# PMODBob.net
KiCad netlist of a schematic drawn in Altium Designer
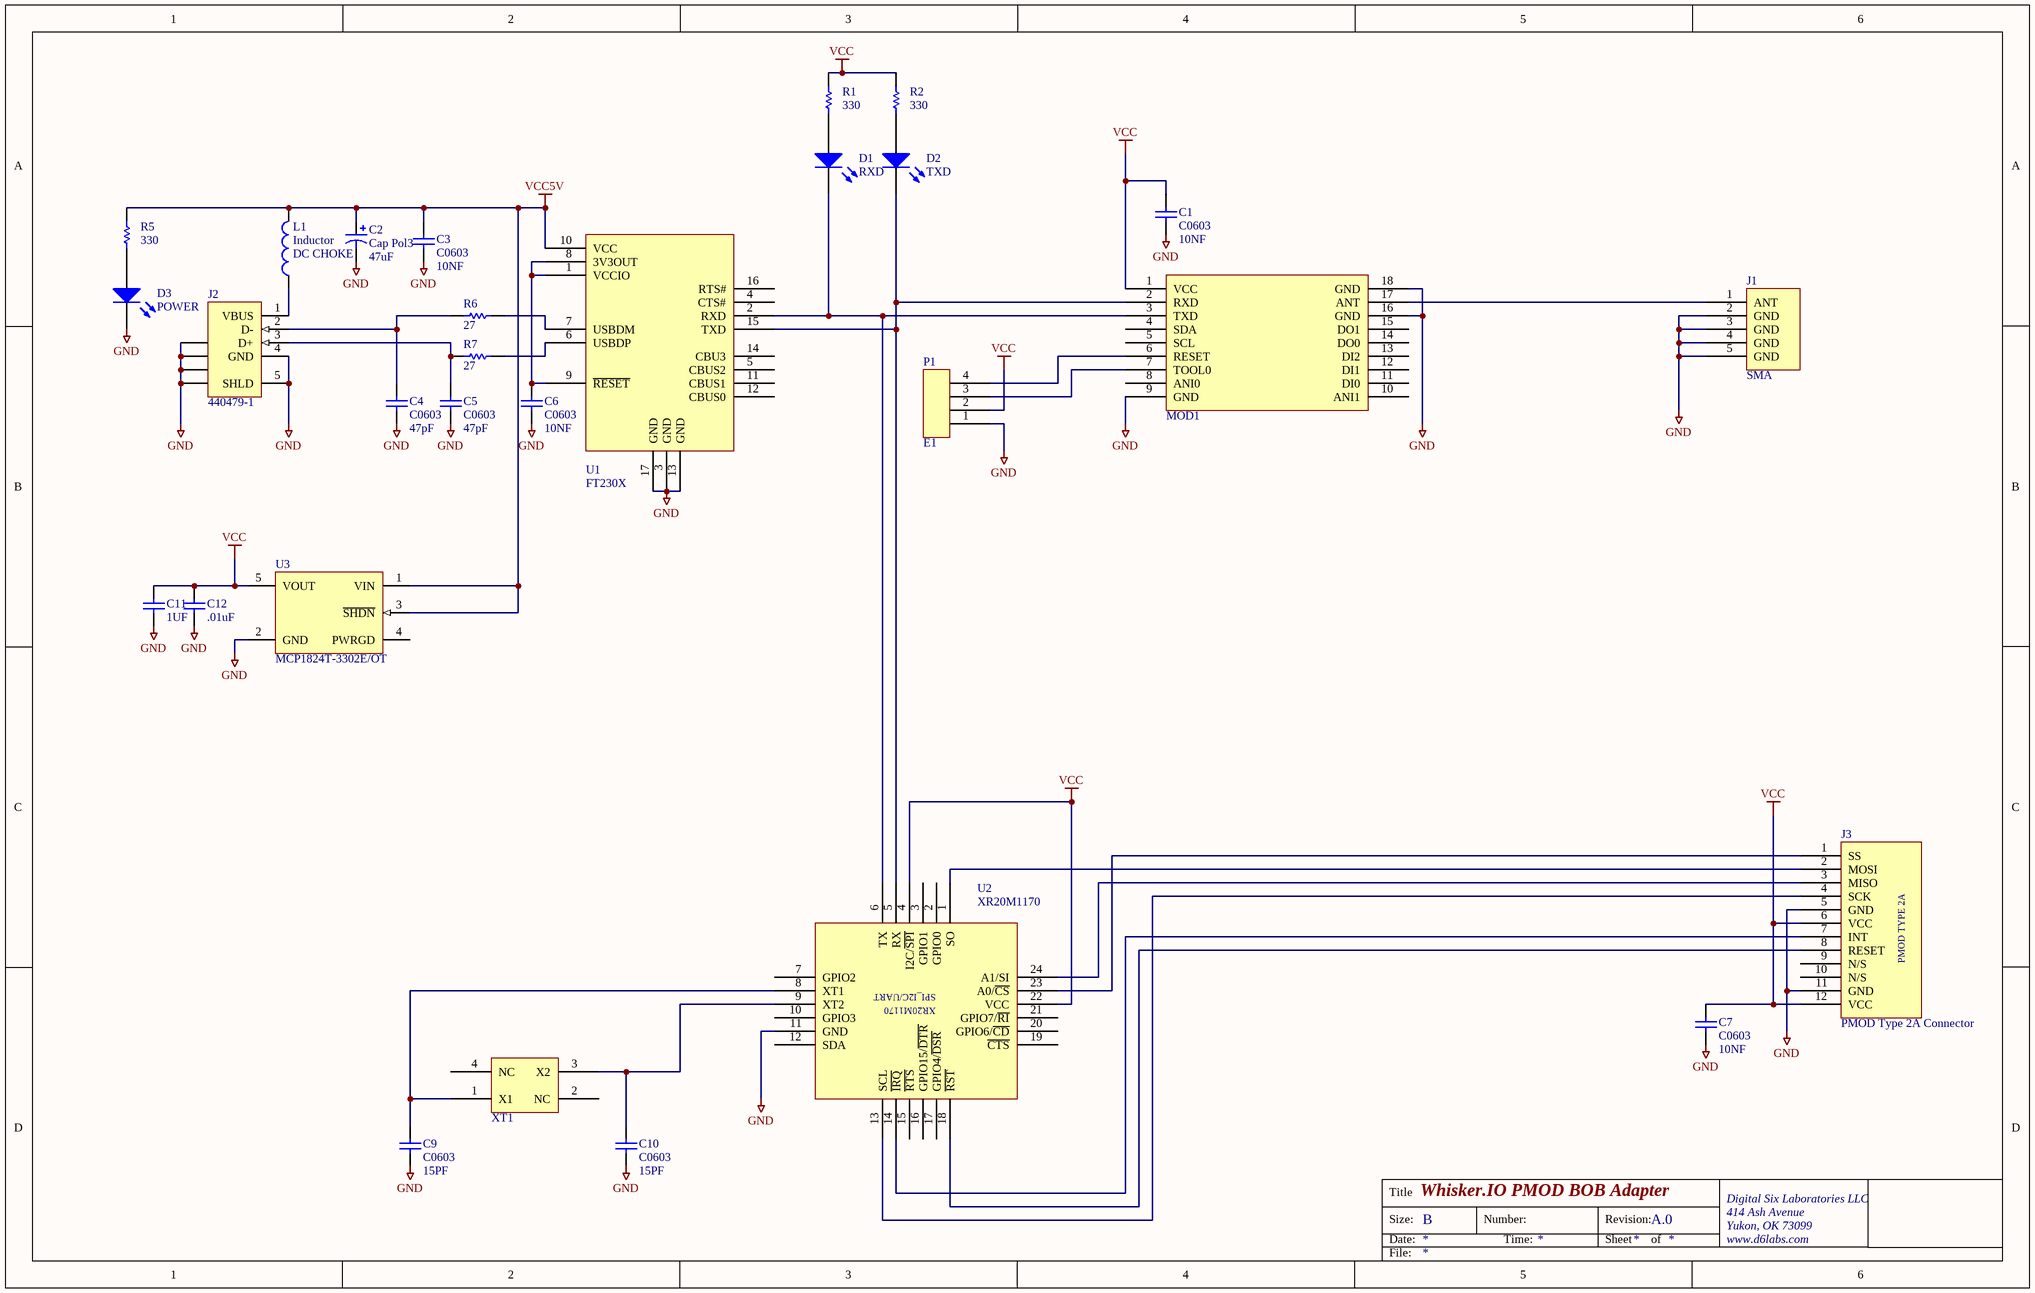
[diagram p0: PMODBob.SchDoc]

(export (version "E")
  (design (tool "Eeschema 10.0.6"))
  (components
    (comp (ref "C1")
      (value "C0603")
      (footprint "0603")
      (description "Ceramic Chip Capacitor - Standard")
      (fields
        (field (name "ALTIUM_VALUE") "10NF")
        (field (name "VENDOR PART NUMBER") "140-CC504B103K-RC")
        (field (name "MANUFACTURER") "XICON")
      )
      (libsource (lib "KEMET Chip Capacitor") (part "C0603"))
    )
    (comp (ref "C2")
      (value "Cap Pol3")
      (footprint "1812")
      (description "Polarized Capacitor (Surface Mount)")
      (fields
        (field (name "ALTIUM_VALUE") "47uF")
        (field (name "VENDOR PART NUMBER") "647-F930J336MBA")
        (field (name "MANUFACTURER") "AVX")
      )
      (libsource (lib "Miscellaneous Devices") (part "Cap Pol3"))
    )
    (comp (ref "C3")
      (value "C0603")
      (footprint "0603")
      (description "Ceramic Chip Capacitor - Standard")
      (fields
        (field (name "ALTIUM_VALUE") "10NF")
        (field (name "VENDOR PART NUMBER") "140-CC504B103K-RC")
        (field (name "MANUFACTURER") "XICON")
      )
      (libsource (lib "KEMET Chip Capacitor") (part "C0603"))
    )
    (comp (ref "C4")
      (value "C0603")
      (footprint "0603")
      (description "Ceramic Chip Capacitor - Standard")
      (fields
        (field (name "ALTIUM_VALUE") "47pF")
        (field (name "VENDOR PART NUMBER") "140-CC504N470J-RC")
        (field (name "MANUFACTURER") "XICON")
      )
      (libsource (lib "KEMET Chip Capacitor") (part "C0603"))
    )
    (comp (ref "C5")
      (value "C0603")
      (footprint "0603")
      (description "Ceramic Chip Capacitor - Standard")
      (fields
        (field (name "ALTIUM_VALUE") "47pF")
        (field (name "VENDOR PART NUMBER") "140-CC504N470J-RC")
        (field (name "MANUFACTURER") "XICON")
      )
      (libsource (lib "KEMET Chip Capacitor") (part "C0603"))
    )
    (comp (ref "C6")
      (value "C0603")
      (footprint "0603")
      (description "Ceramic Chip Capacitor - Standard")
      (fields
        (field (name "ALTIUM_VALUE") "10NF")
        (field (name "VENDOR PART NUMBER") "140-CC504B103K-RC")
        (field (name "MANUFACTURER") "XICON")
      )
      (libsource (lib "KEMET Chip Capacitor") (part "C0603"))
    )
    (comp (ref "C7")
      (value "C0603")
      (footprint "0603")
      (description "Ceramic Chip Capacitor - Standard")
      (fields
        (field (name "ALTIUM_VALUE") "10NF")
        (field (name "VENDOR PART NUMBER") "140-CC504B103K-RC")
        (field (name "MANUFACTURER") "XICON")
      )
      (libsource (lib "KEMET Chip Capacitor") (part "C0603"))
    )
    (comp (ref "C9")
      (value "C0603")
      (footprint "0603")
      (description "Ceramic Chip Capacitor - Standard")
      (fields
        (field (name "ALTIUM_VALUE") "15PF")
        (field (name "VENDOR PART NUMBER") "140-CC504N470J-RC")
        (field (name "MANUFACTURER") "XICON")
      )
      (libsource (lib "KEMET Chip Capacitor") (part "C0603"))
    )
    (comp (ref "C10")
      (value "C0603")
      (footprint "0603")
      (description "Ceramic Chip Capacitor - Standard")
      (fields
        (field (name "ALTIUM_VALUE") "15PF")
        (field (name "VENDOR PART NUMBER") "140-CC504N470J-RC")
        (field (name "MANUFACTURER") "XICON")
      )
      (libsource (lib "KEMET Chip Capacitor") (part "C0603"))
    )
    (comp (ref "C11")
      (value "1UF")
      (footprint "D6_0603_RES")
      (description "Ceramic Chip Capacitor - Standard")
      (fields
        (field (name "MANUFACTURER") "VISHAY")
        (field (name "MANUFACTURER PART NUMBER") "VJ0603A150JXACW1BC")
      )
      (libsource (lib "KEMET Chip Capacitor") (part "C1210"))
    )
    (comp (ref "C12")
      (value ".01uF")
      (footprint "D6_0603_RES")
      (description "Ceramic Chip Capacitor - Standard")
      (fields
        (field (name "MANUFACTURER") "VISHAY")
        (field (name "MANUFACTURER PART NUMBER") "VJ0603A150JXACW1BC")
      )
      (libsource (lib "KEMET Chip Capacitor") (part "C1210"))
    )
    (comp (ref "D1")
      (value "RXD")
      (footprint "3.2X1.6X1.1")
      (description "Typical RED, GREEN, YELLOW, AMBER GaAs LED")
      (fields (field (name "PUBLISHER") "Altium Limited"))
      (libsource (lib "Miscellaneous Devices") (part "LED2"))
    )
    (comp (ref "D2")
      (value "TXD")
      (footprint "3.2X1.6X1.1")
      (description "Typical RED, GREEN, YELLOW, AMBER GaAs LED")
      (fields (field (name "PUBLISHER") "Altium Limited"))
      (libsource (lib "Miscellaneous Devices") (part "LED2"))
    )
    (comp (ref "D3")
      (value "POWER")
      (footprint "3.2X1.6X1.1")
      (description "Typical RED, GREEN, YELLOW, AMBER GaAs LED")
      (fields (field (name "PUBLISHER") "Altium Limited"))
      (libsource (lib "Miscellaneous Devices") (part "LED2"))
    )
    (comp (ref "J1")
      (value "SMA")
      (footprint "RPSMA-EDGEMOUNT")
      (libsource (lib "D6 Connectors") (part "SMA"))
    )
    (comp (ref "J2")
      (value "440479-1")
      (footprint "440479")
      (description "USB 2.0, Right Angle, SMT, AB Type, Receptacle, 5 Position, Black")
      (fields (field (name "PUBLISHER") "Altium Limited"))
      (libsource (lib "AMP Serial Bus USB") (part "440479-1"))
    )
    (comp (ref "J3")
      (value "PMOD Type 2A Connector")
      (footprint "Type2A")
      (libsource (lib "Digilent") (part "PMOD Type 2A Connector"))
    )
    (comp (ref "L1")
      (value "Inductor")
      (footprint "INDC1608L")
      (fields
        (field (name "ALTIUM_VALUE") "DC CHOKE")
        (field (name "MANUFACTURER") "TDK")
        (field (name "MANUFACTURER PART NUMBER") "MPZ1608D101B")
        (field (name "VENDOR PART NUMBER") "810-MPZ1608D101B")
      )
      (libsource (lib "Miscellaneous Devices") (part "Inductor"))
    )
    (comp (ref "MOD1")
      (value "WhiskerModule")
      (footprint "whisker")
      (description "Whisker Footprint")
      (libsource (lib "D6 Labs") (part "WhiskerModule"))
    )
    (comp (ref "P1")
      (value "E1")
      (footprint "2MM4PINHDR")
      (libsource (lib "D6 Connectors") (part "2MM4PINHDR"))
    )
    (comp (ref "R1")
      (value "330")
      (footprint "ERA-0603")
      (fields (field (name "VENDOR PART NUMBER") "301-330-RC") (field (name "MANUFACTURER") "XICON"))
      (libsource (lib "Panasonic Resistor") (part "ERA3Y"))
    )
    (comp (ref "R2")
      (value "330")
      (footprint "ERA-0603")
      (fields (field (name "VENDOR PART NUMBER") "301-330-RC") (field (name "MANUFACTURER") "XICON"))
      (libsource (lib "Panasonic Resistor") (part "ERA3Y"))
    )
    (comp (ref "R5")
      (value "330")
      (footprint "ERA-0603")
      (fields (field (name "VENDOR PART NUMBER") "301-330-RC") (field (name "MANUFACTURER") "XICON"))
      (libsource (lib "Panasonic Resistor") (part "ERA3Y"))
    )
    (comp (ref "R6")
      (value "27")
      (footprint "ERA-0603")
      (fields (field (name "VENDOR PART NUMBER") "301-27-RC") (field (name "MANUFACTURER") "XICON"))
      (libsource (lib "Panasonic Resistor") (part "ERA3Y"))
    )
    (comp (ref "R7")
      (value "27")
      (footprint "ERA-0603")
      (fields (field (name "VENDOR PART NUMBER") "301-27-RC") (field (name "MANUFACTURER") "XICON"))
      (libsource (lib "Panasonic Resistor") (part "ERA3Y"))
    )
    (comp (ref "U1")
      (value "FT230X")
      (footprint "QFN65P400X400X75-16N")
      (description "FT230X USB TO BASIC UART IC")
      (fields (field (name "MANUFACTURER") "FTDI") (field (name "MANUFACTURER PART NUMBER") "FT230XQ"))
      (libsource (lib "FTDI") (part "FT230X"))
    )
    (comp (ref "U2")
      (value "XR20M1170")
      (footprint "QFN50P400X400X80-24N")
      (description "I2C/SPI UART with 64-byte FIFO")
      (fields
        (field (name "MANUFACTURER") "EXAR")
        (field (name "MANUFACTURER PART NUMBER") "XR20M1170IL24-F")
      )
      (libsource (lib "exar") (part "XR20M1170"))
    )
    (comp (ref "U3")
      (value "MCP1824T-3302E/OT")
      (footprint "SOT-23-OT5_N")
      (fields (field (name "PUBLISHER") "Altium Limited"))
      (libsource (lib "Microchip Power Mgt Line Regulator") (part "MCP1824T-3302E/OT"))
    )
    (comp (ref "XT1")
      (value "2.5X3.2MM")
      (footprint "2.5x3.2")
      (description "3.2 X 2.5 MM")
      (libsource (lib "Generic Crystals") (part "2.5X3.2MM"))
    )
  )
  (nets
    (net (code "1") (name "GND") (class "Default")
      (node (ref "C1") (pin "1") (pinfunction "1_1") (pintype "passive"))
      (node (ref "C10") (pin "1") (pinfunction "1_1") (pintype "passive"))
      (node (ref "C11") (pin "1") (pinfunction "1_1") (pintype "passive"))
      (node (ref "C12") (pin "1") (pinfunction "1_1") (pintype "passive"))
      (node (ref "C2") (pin "2") (pinfunction "2_2") (pintype "passive"))
      (node (ref "C3") (pin "1") (pinfunction "1_1") (pintype "passive"))
      (node (ref "C4") (pin "1") (pinfunction "1_1") (pintype "passive"))
      (node (ref "C5") (pin "1") (pinfunction "1_1") (pintype "passive"))
      (node (ref "C6") (pin "1") (pinfunction "1_1") (pintype "passive"))
      (node (ref "C7") (pin "1") (pinfunction "1_1") (pintype "passive"))
      (node (ref "C9") (pin "1") (pinfunction "1_1") (pintype "passive"))
      (node (ref "D3") (pin "2") (pinfunction "K_2") (pintype "passive"))
      (node (ref "J1") (pin "2") (pinfunction "GND_2") (pintype "passive"))
      (node (ref "J1") (pin "3") (pinfunction "GND_3") (pintype "passive"))
      (node (ref "J1") (pin "4") (pinfunction "GND_4") (pintype "passive"))
      (node (ref "J1") (pin "5") (pinfunction "GND_5") (pintype "passive"))
      (node (ref "J2") (pin "4") (pinfunction "GND_4") (pintype "power_in"))
      (node (ref "J2") (pin "5") (pinfunction "SHLD_5") (pintype "passive"))
      (node (ref "J2") (pin "6") (pinfunction "SHLD_6") (pintype "passive"))
      (node (ref "J2") (pin "7") (pinfunction "SHLD_7") (pintype "passive"))
      (node (ref "J2") (pin "8") (pinfunction "SHLD_8") (pintype "passive"))
      (node (ref "J2") (pin "9") (pinfunction "SHLD_9") (pintype "passive"))
      (node (ref "J3") (pin "11") (pinfunction "GND_11") (pintype "passive"))
      (node (ref "J3") (pin "5") (pinfunction "GND_5") (pintype "passive"))
      (node (ref "MOD1") (pin "16") (pinfunction "GND_16") (pintype "passive"))
      (node (ref "MOD1") (pin "18") (pinfunction "GND_18") (pintype "passive"))
      (node (ref "MOD1") (pin "9") (pinfunction "GND_9") (pintype "passive"))
      (node (ref "P1") (pin "1") (pinfunction "RESET_1") (pintype "power_in"))
      (node (ref "U1") (pin "13") (pinfunction "GND_13") (pintype "passive"))
      (node (ref "U1") (pin "17") (pinfunction "GND_17") (pintype "passive"))
      (node (ref "U1") (pin "3") (pinfunction "GND_3") (pintype "passive"))
      (node (ref "U2") (pin "11") (pinfunction "GND_11") (pintype "passive"))
      (node (ref "U3") (pin "2") (pinfunction "GND_2") (pintype "power_in"))
    )
    (net (code "2") (name "Net-(D1-A)") (class "Default")
      (node (ref "D1") (pin "1") (pinfunction "A_1") (pintype "passive"))
      (node (ref "R1") (pin "2") (pinfunction "2_2") (pintype "passive"))
    )
    (net (code "3") (name "Net-(D1-K)") (class "Default")
      (node (ref "D1") (pin "2") (pinfunction "K_2") (pintype "passive"))
      (node (ref "MOD1") (pin "3") (pinfunction "TXD_3") (pintype "passive"))
      (node (ref "U1") (pin "2") (pinfunction "RXD_2") (pintype "passive"))
      (node (ref "U2") (pin "6") (pinfunction "TX_6") (pintype "passive"))
    )
    (net (code "4") (name "Net-(D2-A)") (class "Default")
      (node (ref "D2") (pin "1") (pinfunction "A_1") (pintype "passive"))
      (node (ref "R2") (pin "2") (pinfunction "2_2") (pintype "passive"))
    )
    (net (code "5") (name "Net-(D2-K)") (class "Default")
      (node (ref "D2") (pin "2") (pinfunction "K_2") (pintype "passive"))
      (node (ref "MOD1") (pin "2") (pinfunction "RXD_2") (pintype "passive"))
      (node (ref "U1") (pin "15") (pinfunction "TXD_15") (pintype "passive"))
      (node (ref "U2") (pin "5") (pinfunction "RX_5") (pintype "passive"))
    )
    (net (code "6") (name "Net-(D3-A)") (class "Default")
      (node (ref "D3") (pin "1") (pinfunction "A_1") (pintype "passive"))
      (node (ref "R5") (pin "2") (pinfunction "2_2") (pintype "passive"))
    )
    (net (code "7") (name "Net-(J1-ANT)") (class "Default")
      (node (ref "J1") (pin "1") (pinfunction "ANT_1") (pintype "passive"))
      (node (ref "MOD1") (pin "17") (pinfunction "ANT_17") (pintype "passive"))
    )
    (net (code "8") (name "Net-(J2-D+)") (class "Default")
      (node (ref "C5") (pin "2") (pinfunction "2_2") (pintype "passive"))
      (node (ref "J2") (pin "3") (pinfunction "D+_3") (pintype "input"))
      (node (ref "R7") (pin "2") (pinfunction "2_2") (pintype "passive"))
    )
    (net (code "9") (name "Net-(J2-D-)") (class "Default")
      (node (ref "C4") (pin "2") (pinfunction "2_2") (pintype "passive"))
      (node (ref "J2") (pin "2") (pinfunction "D-_2") (pintype "input"))
      (node (ref "R6") (pin "2") (pinfunction "2_2") (pintype "passive"))
    )
    (net (code "10") (name "Net-(J2-VBUS)") (class "Default")
      (node (ref "J2") (pin "1") (pinfunction "VBUS_1") (pintype "power_in"))
      (node (ref "L1") (pin "1") (pinfunction "1_1") (pintype "passive"))
    )
    (net (code "11") (name "Net-(J3-INT)") (class "Default")
      (node (ref "J3") (pin "7") (pinfunction "INT_7") (pintype "passive"))
      (node (ref "U2") (pin "14") (pinfunction "~{IRQ}_14") (pintype "passive"))
    )
    (net (code "12") (name "Net-(J3-MISO)") (class "Default")
      (node (ref "J3") (pin "3") (pinfunction "MISO_3") (pintype "passive"))
      (node (ref "U2") (pin "24") (pinfunction "A1/SI_24") (pintype "passive"))
    )
    (net (code "13") (name "Net-(J3-MOSI)") (class "Default")
      (node (ref "J3") (pin "2") (pinfunction "MOSI_2") (pintype "passive"))
      (node (ref "U2") (pin "1") (pinfunction "SO_1") (pintype "passive"))
    )
    (net (code "14") (name "Net-(J3-RESET)") (class "Default")
      (node (ref "J3") (pin "8") (pinfunction "RESET_8") (pintype "passive"))
      (node (ref "U2") (pin "18") (pinfunction "~{RST}_18") (pintype "passive"))
    )
    (net (code "15") (name "Net-(J3-SCK)") (class "Default")
      (node (ref "J3") (pin "4") (pinfunction "SCK_4") (pintype "passive"))
      (node (ref "U2") (pin "13") (pinfunction "SCL_13") (pintype "passive"))
    )
    (net (code "16") (name "Net-(J3-SS)") (class "Default")
      (node (ref "J3") (pin "1") (pinfunction "SS_1") (pintype "passive"))
      (node (ref "U2") (pin "23") (pinfunction "A0/~{CS}_23") (pintype "passive"))
    )
    (net (code "17") (name "Net-(MOD1-RESET)") (class "Default")
      (node (ref "MOD1") (pin "6") (pinfunction "RESET_6") (pintype "passive"))
      (node (ref "P1") (pin "4") (pinfunction "RESET_4") (pintype "power_in"))
    )
    (net (code "18") (name "Net-(MOD1-TOOL0)") (class "Default")
      (node (ref "MOD1") (pin "7") (pinfunction "TOOL0_7") (pintype "passive"))
      (node (ref "P1") (pin "3") (pinfunction "RESET_3") (pintype "power_in"))
    )
    (net (code "19") (name "Net-(U1-3V3OUT)") (class "Default")
      (node (ref "C6") (pin "2") (pinfunction "2_2") (pintype "passive"))
      (node (ref "U1") (pin "1") (pinfunction "VCCIO_1") (pintype "passive"))
      (node (ref "U1") (pin "8") (pinfunction "3V3OUT_8") (pintype "passive"))
      (node (ref "U1") (pin "9") (pinfunction "~{RESET}_9") (pintype "passive"))
    )
    (net (code "20") (name "Net-(U1-USBDM)") (class "Default")
      (node (ref "R6") (pin "1") (pinfunction "1_1") (pintype "passive"))
      (node (ref "U1") (pin "7") (pinfunction "USBDM_7") (pintype "passive"))
    )
    (net (code "21") (name "Net-(U1-USBDP)") (class "Default")
      (node (ref "R7") (pin "1") (pinfunction "1_1") (pintype "passive"))
      (node (ref "U1") (pin "6") (pinfunction "USBDP_6") (pintype "passive"))
    )
    (net (code "22") (name "Net-(U2-XT1)") (class "Default")
      (node (ref "C9") (pin "2") (pinfunction "2_2") (pintype "passive"))
      (node (ref "U2") (pin "8") (pinfunction "XT1_8") (pintype "passive"))
      (node (ref "XT1") (pin "1") (pinfunction "X1_1") (pintype "passive"))
    )
    (net (code "23") (name "Net-(U2-XT2)") (class "Default")
      (node (ref "C10") (pin "2") (pinfunction "2_2") (pintype "passive"))
      (node (ref "U2") (pin "9") (pinfunction "XT2_9") (pintype "passive"))
      (node (ref "XT1") (pin "3") (pinfunction "X2_3") (pintype "passive"))
    )
    (net (code "24") (name "VCC") (class "Default")
      (node (ref "C1") (pin "2") (pinfunction "2_2") (pintype "passive"))
      (node (ref "C11") (pin "2") (pinfunction "2_2") (pintype "passive"))
      (node (ref "C12") (pin "2") (pinfunction "2_2") (pintype "passive"))
      (node (ref "C7") (pin "2") (pinfunction "2_2") (pintype "passive"))
      (node (ref "J3") (pin "12") (pinfunction "VCC_12") (pintype "passive"))
      (node (ref "J3") (pin "6") (pinfunction "VCC_6") (pintype "passive"))
      (node (ref "MOD1") (pin "1") (pinfunction "VCC_1") (pintype "passive"))
      (node (ref "P1") (pin "2") (pinfunction "RESET_2") (pintype "power_in"))
      (node (ref "R1") (pin "1") (pinfunction "1_1") (pintype "passive"))
      (node (ref "R2") (pin "1") (pinfunction "1_1") (pintype "passive"))
      (node (ref "U2") (pin "22") (pinfunction "VCC_22") (pintype "passive"))
      (node (ref "U2") (pin "4") (pinfunction "I2C/~{SPI}_4") (pintype "passive"))
      (node (ref "U3") (pin "5") (pinfunction "VOUT_5") (pintype "power_in"))
    )
    (net (code "25") (name "VCC5V") (class "Default")
      (node (ref "C2") (pin "1") (pinfunction "1_1") (pintype "passive"))
      (node (ref "C3") (pin "2") (pinfunction "2_2") (pintype "passive"))
      (node (ref "L1") (pin "2") (pinfunction "2_2") (pintype "passive"))
      (node (ref "R5") (pin "1") (pinfunction "1_1") (pintype "passive"))
      (node (ref "U1") (pin "10") (pinfunction "VCC_10") (pintype "passive"))
      (node (ref "U3") (pin "1") (pinfunction "VIN_1") (pintype "power_in"))
      (node (ref "U3") (pin "3") (pinfunction "~{SHDN}_3") (pintype "input"))
    )
    (net (code "26") (name "unconnected-(J3-N{slash}S-Pad9)") (class "Default")
      (node (ref "J3") (pin "9") (pinfunction "N/S_9") (pintype "passive"))
    )
    (net (code "27") (name "unconnected-(J3-N{slash}S-Pad10)") (class "Default")
      (node (ref "J3") (pin "10") (pinfunction "N/S_10") (pintype "passive"))
    )
    (net (code "28") (name "unconnected-(MOD1-ANI0-Pad8)") (class "Default")
      (node (ref "MOD1") (pin "8") (pinfunction "ANI0_8") (pintype "passive"))
    )
    (net (code "29") (name "unconnected-(MOD1-ANI1-Pad10)") (class "Default")
      (node (ref "MOD1") (pin "10") (pinfunction "ANI1_10") (pintype "passive"))
    )
    (net (code "30") (name "unconnected-(MOD1-DI0-Pad11)") (class "Default")
      (node (ref "MOD1") (pin "11") (pinfunction "DI0_11") (pintype "passive"))
    )
    (net (code "31") (name "unconnected-(MOD1-DI1-Pad12)") (class "Default")
      (node (ref "MOD1") (pin "12") (pinfunction "DI1_12") (pintype "passive"))
    )
    (net (code "32") (name "unconnected-(MOD1-DI2-Pad13)") (class "Default")
      (node (ref "MOD1") (pin "13") (pinfunction "DI2_13") (pintype "passive"))
    )
    (net (code "33") (name "unconnected-(MOD1-DO0-Pad14)") (class "Default")
      (node (ref "MOD1") (pin "14") (pinfunction "DO0_14") (pintype "passive"))
    )
    (net (code "34") (name "unconnected-(MOD1-DO1-Pad15)") (class "Default")
      (node (ref "MOD1") (pin "15") (pinfunction "DO1_15") (pintype "passive"))
    )
    (net (code "35") (name "unconnected-(MOD1-SCL-Pad5)") (class "Default")
      (node (ref "MOD1") (pin "5") (pinfunction "SCL_5") (pintype "passive"))
    )
    (net (code "36") (name "unconnected-(MOD1-SDA-Pad4)") (class "Default")
      (node (ref "MOD1") (pin "4") (pinfunction "SDA_4") (pintype "passive"))
    )
    (net (code "37") (name "unconnected-(U1-CBU3-Pad14)") (class "Default")
      (node (ref "U1") (pin "14") (pinfunction "CBU3_14") (pintype "passive"))
    )
    (net (code "38") (name "unconnected-(U1-CBUS0-Pad12)") (class "Default")
      (node (ref "U1") (pin "12") (pinfunction "CBUS0_12") (pintype "passive"))
    )
    (net (code "39") (name "unconnected-(U1-CBUS1-Pad11)") (class "Default")
      (node (ref "U1") (pin "11") (pinfunction "CBUS1_11") (pintype "passive"))
    )
    (net (code "40") (name "unconnected-(U1-CBUS2-Pad5)") (class "Default")
      (node (ref "U1") (pin "5") (pinfunction "CBUS2_5") (pintype "passive"))
    )
    (net (code "41") (name "unconnected-(U1-CTS#-Pad4)") (class "Default")
      (node (ref "U1") (pin "4") (pinfunction "CTS#_4") (pintype "passive"))
    )
    (net (code "42") (name "unconnected-(U1-RTS#-Pad16)") (class "Default")
      (node (ref "U1") (pin "16") (pinfunction "RTS#_16") (pintype "passive"))
    )
    (net (code "43") (name "unconnected-(U2-GPIO0-Pad2)") (class "Default")
      (node (ref "U2") (pin "2") (pinfunction "GPIO0_2") (pintype "passive"))
    )
    (net (code "44") (name "unconnected-(U2-GPIO1-Pad3)") (class "Default")
      (node (ref "U2") (pin "3") (pinfunction "GPIO1_3") (pintype "passive"))
    )
    (net (code "45") (name "unconnected-(U2-GPIO2-Pad7)") (class "Default")
      (node (ref "U2") (pin "7") (pinfunction "GPIO2_7") (pintype "passive"))
    )
    (net (code "46") (name "unconnected-(U2-GPIO3-Pad10)") (class "Default")
      (node (ref "U2") (pin "10") (pinfunction "GPIO3_10") (pintype "passive"))
    )
    (net (code "47") (name "unconnected-(U2-GPIO4{slash}~{DSR}-Pad17)") (class "Default")
      (node (ref "U2") (pin "17") (pinfunction "GPIO4/~{DSR}_17") (pintype "passive"))
    )
    (net (code "48") (name "unconnected-(U2-GPIO6{slash}~{CD}-Pad20)") (class "Default")
      (node (ref "U2") (pin "20") (pinfunction "GPIO6/~{CD}_20") (pintype "passive"))
    )
    (net (code "49") (name "unconnected-(U2-GPIO7{slash}~{RI}-Pad21)") (class "Default")
      (node (ref "U2") (pin "21") (pinfunction "GPIO7/~{RI}_21") (pintype "passive"))
    )
    (net (code "50") (name "unconnected-(U2-GPIO15{slash}~{DTR}-Pad16)") (class "Default")
      (node (ref "U2") (pin "16") (pinfunction "GPIO15/~{DTR}_16") (pintype "passive"))
    )
    (net (code "51") (name "unconnected-(U2-SDA-Pad12)") (class "Default")
      (node (ref "U2") (pin "12") (pinfunction "SDA_12") (pintype "passive"))
    )
    (net (code "52") (name "unconnected-(U2-~{CTS}-Pad19)") (class "Default")
      (node (ref "U2") (pin "19") (pinfunction "~{CTS}_19") (pintype "passive"))
    )
    (net (code "53") (name "unconnected-(U2-~{RTS}-Pad15)") (class "Default")
      (node (ref "U2") (pin "15") (pinfunction "~{RTS}_15") (pintype "passive"))
    )
    (net (code "54") (name "unconnected-(U3-PWRGD-Pad4)") (class "Default")
      (node (ref "U3") (pin "4") (pinfunction "PWRGD_4") (pintype "power_in"))
    )
    (net (code "55") (name "unconnected-(XT1-NC-Pad2)") (class "Default")
      (node (ref "XT1") (pin "2") (pinfunction "NC_2") (pintype "passive"))
    )
    (net (code "56") (name "unconnected-(XT1-NC-Pad4)") (class "Default")
      (node (ref "XT1") (pin "4") (pinfunction "NC_4") (pintype "passive"))
    )
  )
)
